# LCD_TOUCH.net
KiCad netlist of a schematic drawn in Altium Designer
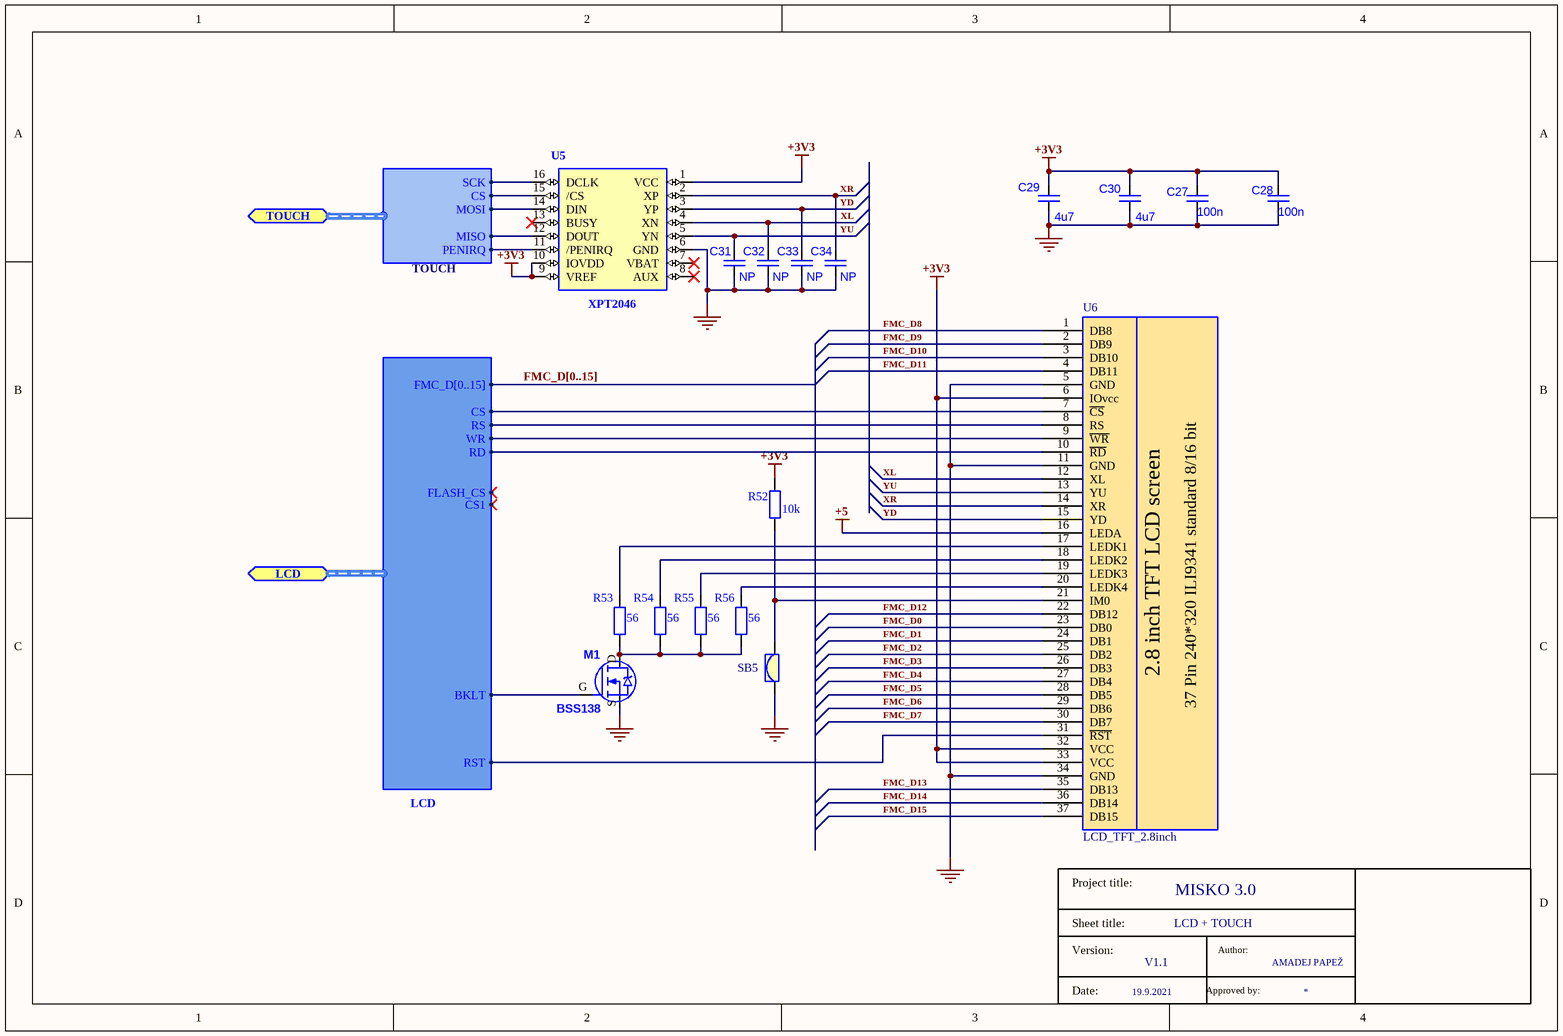
[diagram p0: LCD + TOUCH .SchDoc]

(export (version "E")
  (design (tool "Eeschema 10.0.6"))
  (components
    (comp (ref "C27")
      (value "100n")
      (footprint "C0603")
      (description "Capacitor")
      (libsource (lib "MISKO3_V6") (part "C"))
    )
    (comp (ref "C28")
      (value "100n")
      (footprint "C0603")
      (description "Capacitor")
      (libsource (lib "MISKO3_V6") (part "C"))
    )
    (comp (ref "C29")
      (value "4u7")
      (footprint "C0603")
      (description "Capacitor")
      (libsource (lib "MISKO3_V6") (part "C"))
    )
    (comp (ref "C30")
      (value "4u7")
      (footprint "C0603")
      (description "Capacitor")
      (libsource (lib "MISKO3_V6") (part "C"))
    )
    (comp (ref "C31")
      (value "NP")
      (footprint "C0603")
      (description "Capacitor")
      (libsource (lib "MISKO3_V6") (part "C"))
    )
    (comp (ref "C32")
      (value "NP")
      (footprint "C0603")
      (description "Capacitor")
      (libsource (lib "MISKO3_V6") (part "C"))
    )
    (comp (ref "C33")
      (value "NP")
      (footprint "C0603")
      (description "Capacitor")
      (libsource (lib "MISKO3_V6") (part "C"))
    )
    (comp (ref "C34")
      (value "NP")
      (footprint "C0603")
      (description "Capacitor")
      (libsource (lib "MISKO3_V6") (part "C"))
    )
    (comp (ref "M1")
      (value "BSS138")
      (footprint "SOT23-3_L")
      (description "BSH103-T/R (NMOS)")
      (libsource (lib "MISKO3_V6") (part "BSH103"))
    )
    (comp (ref "R52")
      (value "10k")
      (footprint "R1608_0603I_L")
      (description "R")
      (libsource (lib "") (part "R_1"))
    )
    (comp (ref "R53")
      (value "56")
      (footprint "R1608_0603I_L")
      (description "R")
      (libsource (lib "MISKO3_V6") (part "R"))
    )
    (comp (ref "R54")
      (value "56")
      (footprint "R1608_0603I_L")
      (description "R")
      (libsource (lib "MISKO3_V6") (part "R"))
    )
    (comp (ref "R55")
      (value "56")
      (footprint "R1608_0603I_L")
      (description "R")
      (libsource (lib "MISKO3_V6") (part "R"))
    )
    (comp (ref "R56")
      (value "56")
      (footprint "R1608_0603I_L")
      (description "R")
      (libsource (lib "MISKO3_V6") (part "R"))
    )
    (comp (ref "SB5")
      (value "SD_JUMP")
      (footprint "SOLDER_JUMPER")
      (libsource (lib "MISKO3_V6") (part "SD_JUMP"))
    )
    (comp (ref "T7") (value "~") (libsource (lib "MISKO3_V6") (part "Title block")))
    (comp (ref "U5")
      (value "XPT2046")
      (footprint "TSSOP16")
      (description "LCD touch controller")
      (fields (field (name "MF") "Xptek"))
      (libsource (lib "MISKO3_V6") (part "XPT2046"))
    )
    (comp (ref "U6")
      (value "LCD_TFT_2.8inch")
      (footprint "LCD_TFT_2.8inch")
      (libsource (lib "MISKO3_V6") (part "LCD_TFT_2.8inch"))
    )
  )
  (nets
    (net (code "3") (name "+3V3") (class "Default")
      (node (ref "C27") (pin "2") (pinfunction "2_2") (pintype "passive"))
      (node (ref "C28") (pin "2") (pinfunction "2_2") (pintype "passive"))
      (node (ref "C29") (pin "2") (pinfunction "2_2") (pintype "passive"))
      (node (ref "C30") (pin "2") (pinfunction "2_2") (pintype "passive"))
      (node (ref "R52") (pin "2") (pintype "passive"))
      (node (ref "U5") (pin "1") (pinfunction "VCC_1") (pintype "bidirectional"))
      (node (ref "U5") (pin "10") (pinfunction "IOVDD_10") (pintype "bidirectional"))
      (node (ref "U5") (pin "9") (pinfunction "VREF_9") (pintype "bidirectional"))
      (node (ref "U6") (pin "32") (pinfunction "VCC_32") (pintype "passive"))
      (node (ref "U6") (pin "33") (pinfunction "VCC_33") (pintype "passive"))
      (node (ref "U6") (pin "6") (pinfunction "IOvcc_6") (pintype "passive"))
    )
    (net (code "4") (name "+5") (class "Default")
      (node (ref "U6") (pin "16") (pinfunction "LEDA_16") (pintype "passive"))
    )
    (net (code "5") (name "/BKLT") (class "Default")
      (node (ref "M1") (pin "G") (pinfunction "G_G") (pintype "passive"))
    )
    (net (code "6") (name "/FMC_D0") (class "Default")
      (node (ref "U6") (pin "23") (pinfunction "DB0_23") (pintype "passive"))
    )
    (net (code "7") (name "/FMC_D1") (class "Default")
      (node (ref "U6") (pin "24") (pinfunction "DB1_24") (pintype "passive"))
    )
    (net (code "8") (name "/FMC_D2") (class "Default")
      (node (ref "U6") (pin "25") (pinfunction "DB2_25") (pintype "passive"))
    )
    (net (code "9") (name "/FMC_D3") (class "Default")
      (node (ref "U6") (pin "26") (pinfunction "DB3_26") (pintype "passive"))
    )
    (net (code "10") (name "/FMC_D4") (class "Default")
      (node (ref "U6") (pin "27") (pinfunction "DB4_27") (pintype "passive"))
    )
    (net (code "11") (name "/FMC_D5") (class "Default")
      (node (ref "U6") (pin "28") (pinfunction "DB5_28") (pintype "passive"))
    )
    (net (code "12") (name "/FMC_D6") (class "Default")
      (node (ref "U6") (pin "29") (pinfunction "DB6_29") (pintype "passive"))
    )
    (net (code "13") (name "/FMC_D7") (class "Default")
      (node (ref "U6") (pin "30") (pinfunction "DB7_30") (pintype "passive"))
    )
    (net (code "14") (name "/FMC_D8") (class "Default")
      (node (ref "U6") (pin "1") (pinfunction "DB8_1") (pintype "passive"))
    )
    (net (code "15") (name "/FMC_D9") (class "Default")
      (node (ref "U6") (pin "2") (pinfunction "DB9_2") (pintype "passive"))
    )
    (net (code "16") (name "/FMC_D10") (class "Default")
      (node (ref "U6") (pin "3") (pinfunction "DB10_3") (pintype "passive"))
    )
    (net (code "17") (name "/FMC_D11") (class "Default")
      (node (ref "U6") (pin "4") (pinfunction "DB11_4") (pintype "passive"))
    )
    (net (code "18") (name "/FMC_D12") (class "Default")
      (node (ref "U6") (pin "22") (pinfunction "DB12_22") (pintype "passive"))
    )
    (net (code "19") (name "/FMC_D13") (class "Default")
      (node (ref "U6") (pin "35") (pinfunction "DB13_35") (pintype "passive"))
    )
    (net (code "20") (name "/FMC_D14") (class "Default")
      (node (ref "U6") (pin "36") (pinfunction "DB14_36") (pintype "passive"))
    )
    (net (code "21") (name "/FMC_D15") (class "Default")
      (node (ref "U6") (pin "37") (pinfunction "DB15_37") (pintype "passive"))
    )
    (net (code "23") (name "/MISO") (class "Default")
      (node (ref "U5") (pin "12") (pinfunction "DOUT_12") (pintype "bidirectional"))
    )
    (net (code "24") (name "/MOSI") (class "Default")
      (node (ref "U5") (pin "14") (pinfunction "DIN_14") (pintype "bidirectional"))
    )
    (net (code "25") (name "/PENIRQ") (class "Default")
      (node (ref "U5") (pin "11") (pinfunction "/PENIRQ_11") (pintype "bidirectional"))
    )
    (net (code "26") (name "/RD") (class "Default")
      (node (ref "U6") (pin "10") (pinfunction "~{RD}_10") (pintype "passive"))
    )
    (net (code "27") (name "/RS") (class "Default")
      (node (ref "U6") (pin "8") (pinfunction "RS_8") (pintype "passive"))
    )
    (net (code "28") (name "/RST") (class "Default")
      (node (ref "U6") (pin "31") (pinfunction "~{RST}_31") (pintype "passive"))
    )
    (net (code "29") (name "/SCK") (class "Default")
      (node (ref "U5") (pin "16") (pinfunction "DCLK_16") (pintype "bidirectional"))
    )
    (net (code "30") (name "/WR") (class "Default")
      (node (ref "U6") (pin "9") (pinfunction "~{WR}_9") (pintype "passive"))
    )
    (net (code "31") (name "/XL") (class "Default")
      (node (ref "C32") (pin "2") (pinfunction "2_2") (pintype "passive"))
      (node (ref "U5") (pin "4") (pinfunction "XN_4") (pintype "bidirectional"))
      (node (ref "U6") (pin "12") (pinfunction "XL_12") (pintype "passive"))
    )
    (net (code "32") (name "/XR") (class "Default")
      (node (ref "C34") (pin "2") (pinfunction "2_2") (pintype "passive"))
      (node (ref "U5") (pin "2") (pinfunction "XP_2") (pintype "bidirectional"))
      (node (ref "U6") (pin "14") (pinfunction "XR_14") (pintype "passive"))
    )
    (net (code "33") (name "/YD") (class "Default")
      (node (ref "C33") (pin "2") (pinfunction "2_2") (pintype "passive"))
      (node (ref "U5") (pin "3") (pinfunction "YP_3") (pintype "bidirectional"))
      (node (ref "U6") (pin "15") (pinfunction "YD_15") (pintype "passive"))
    )
    (net (code "34") (name "/YU") (class "Default")
      (node (ref "C31") (pin "2") (pinfunction "2_2") (pintype "passive"))
      (node (ref "U5") (pin "5") (pinfunction "YN_5") (pintype "bidirectional"))
      (node (ref "U6") (pin "13") (pinfunction "YU_13") (pintype "passive"))
    )
    (net (code "37") (name "GND") (class "Default")
      (node (ref "C27") (pin "1") (pinfunction "1_1") (pintype "passive"))
      (node (ref "C28") (pin "1") (pinfunction "1_1") (pintype "passive"))
      (node (ref "C29") (pin "1") (pinfunction "1_1") (pintype "passive"))
      (node (ref "C30") (pin "1") (pinfunction "1_1") (pintype "passive"))
      (node (ref "C31") (pin "1") (pinfunction "1_1") (pintype "passive"))
      (node (ref "C32") (pin "1") (pinfunction "1_1") (pintype "passive"))
      (node (ref "C33") (pin "1") (pinfunction "1_1") (pintype "passive"))
      (node (ref "C34") (pin "1") (pinfunction "1_1") (pintype "passive"))
      (node (ref "M1") (pin "S") (pinfunction "S_S") (pintype "passive"))
      (node (ref "SB5") (pin "1") (pinfunction "37_1") (pintype "passive"))
      (node (ref "U5") (pin "6") (pinfunction "GND_6") (pintype "bidirectional"))
      (node (ref "U6") (pin "11") (pinfunction "GND_11") (pintype "passive"))
      (node (ref "U6") (pin "34") (pinfunction "GND_34") (pintype "passive"))
      (node (ref "U6") (pin "5") (pinfunction "GND_5") (pintype "passive"))
    )
    (net (code "38") (name "Net-(M1-PadD)") (class "Default")
      (node (ref "M1") (pin "D") (pinfunction "D_D") (pintype "passive"))
      (node (ref "R53") (pin "1") (pintype "passive"))
      (node (ref "R54") (pin "1") (pintype "passive"))
      (node (ref "R55") (pin "1") (pintype "passive"))
      (node (ref "R56") (pin "1") (pintype "passive"))
    )
    (net (code "39") (name "Net-(SB5-38)") (class "Default")
      (node (ref "R52") (pin "1") (pintype "passive"))
      (node (ref "SB5") (pin "2") (pinfunction "38_2") (pintype "passive"))
      (node (ref "U6") (pin "21") (pinfunction "IM0_21") (pintype "passive"))
    )
    (net (code "40") (name "Net-(U6-LEDK1)") (class "Default")
      (node (ref "R53") (pin "2") (pintype "passive"))
      (node (ref "U6") (pin "17") (pinfunction "LEDK1_17") (pintype "passive"))
    )
    (net (code "41") (name "Net-(U6-LEDK2)") (class "Default")
      (node (ref "R54") (pin "2") (pintype "passive"))
      (node (ref "U6") (pin "18") (pinfunction "LEDK2_18") (pintype "passive"))
    )
    (net (code "42") (name "Net-(U6-LEDK3)") (class "Default")
      (node (ref "R55") (pin "2") (pintype "passive"))
      (node (ref "U6") (pin "19") (pinfunction "LEDK3_19") (pintype "passive"))
    )
    (net (code "43") (name "Net-(U6-LEDK4)") (class "Default")
      (node (ref "R56") (pin "2") (pintype "passive"))
      (node (ref "U6") (pin "20") (pinfunction "LEDK4_20") (pintype "passive"))
    )
    (net (code "44") (name "unconnected-(U5-AUX-Pad8)") (class "Default")
      (node (ref "U5") (pin "8") (pinfunction "AUX_8") (pintype "bidirectional+no_connect"))
    )
    (net (code "45") (name "unconnected-(U5-BUSY-Pad13)") (class "Default")
      (node (ref "U5") (pin "13") (pinfunction "BUSY_13") (pintype "bidirectional+no_connect"))
    )
    (net (code "46") (name "unconnected-(U5-VBAT-Pad7)") (class "Default")
      (node (ref "U5") (pin "7") (pinfunction "VBAT_7") (pintype "bidirectional+no_connect"))
    )
    (net (code "47") (name "unconnected-(U5-{slash}CS-Pad15)") (class "Default")
      (node (ref "U5") (pin "15") (pinfunction "/CS_15") (pintype "bidirectional"))
    )
    (net (code "48") (name "unconnected-(U6-~{CS}-Pad7)") (class "Default")
      (node (ref "U6") (pin "7") (pinfunction "~{CS}_7") (pintype "passive"))
    )
  )
)
